# untitled.net
KiCad netlist of a schematic drawn in Altium Designer
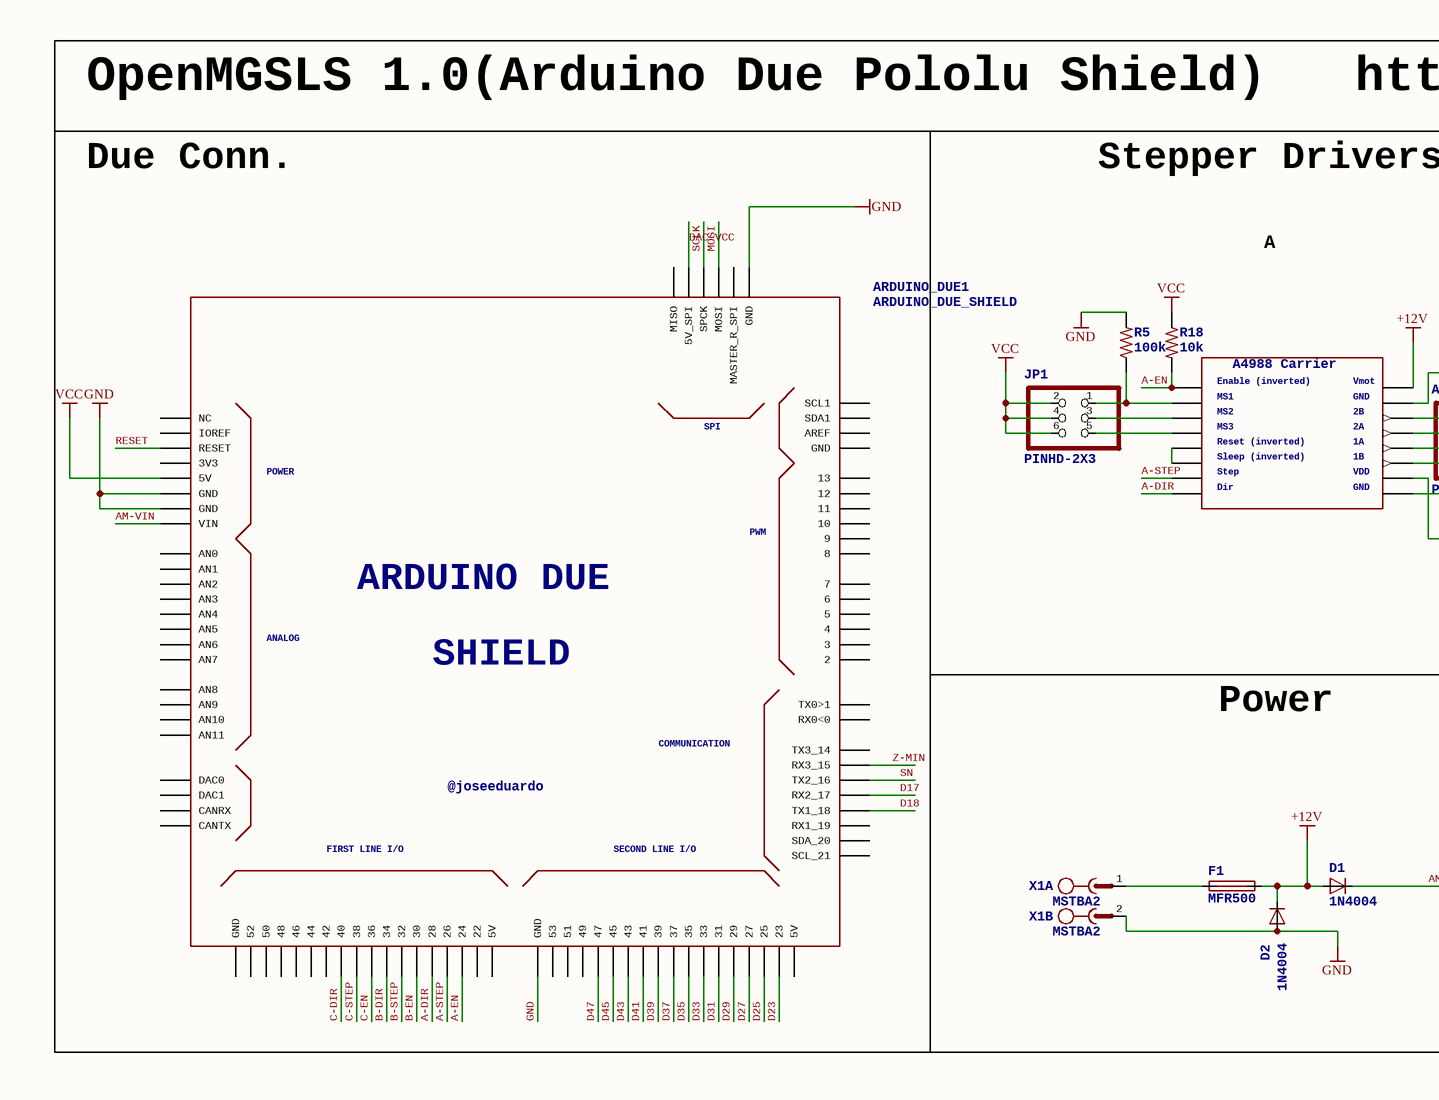
[diagram p0: untitled.SchDoc, left]
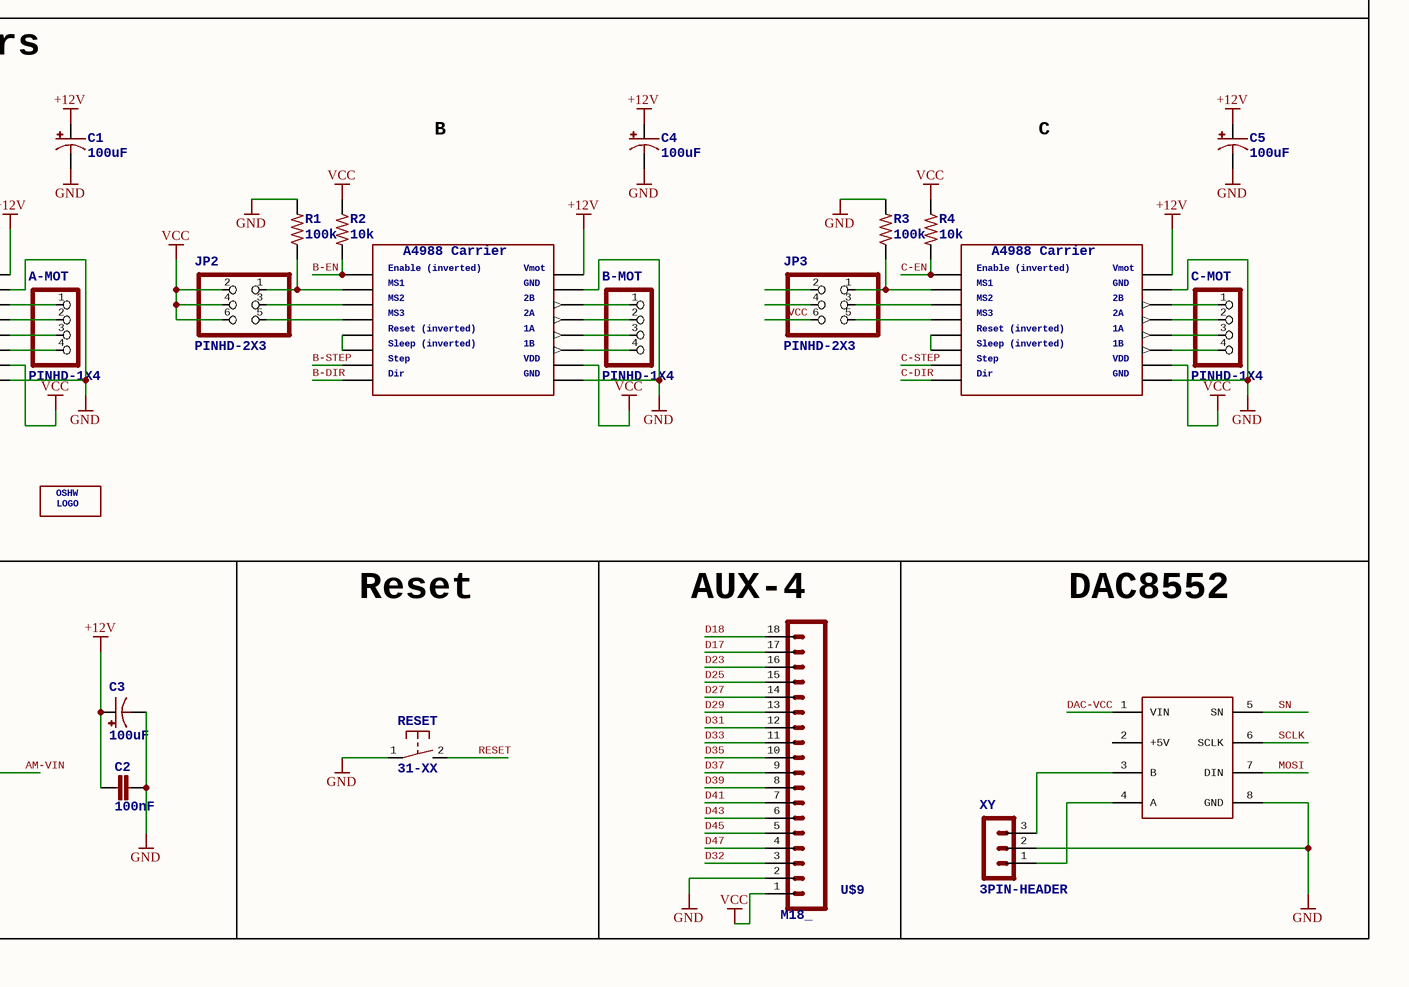
[diagram p1: untitled.SchDoc, right]

(export (version "E")
  (design (tool "Eeschema 10.0.6"))
  (components
    (comp (ref "A-MOT")
      (value "PINHD-1X4")
      (footprint "1X04")
      (description "PIN HEADER")
      (libsource (lib "RepRapjr") (part "PINHD-1X4"))
    )
    (comp (ref "ARDUINO_DUE1")
      (value "ARDUINO_DUE_SHIELD")
      (footprint "ARDUINO_DUE_SHIELD")
      (fields
        (field (name "ARDUINODUE") "ARDUINO DUE")
        (field (name "SHIELD") "SHIELD")
        (field (name "PWM") "PWM")
        (field (name "POWER") "POWER")
        (field (name "ANALOG") "ANALOG")
        (field (name "FIRSTLINEI/O") "FIRST LINE I/O")
        (field (name "SECONDLINEI/O") "SECOND LINE I/O")
        (field (name "COMMUNICATION") "COMMUNICATION")
        (field (name "SPI") "SPI")
        (field (name "@JOSEEDUARDO") "@joseeduardo")
      )
      (libsource (lib "RepRapjr") (part "ARDUINO_DUE_SHIELD"))
    )
    (comp (ref "B-MOT")
      (value "PINHD-1X4")
      (footprint "1X04")
      (description "PIN HEADER")
      (libsource (lib "RepRapjr") (part "PINHD-1X4"))
    )
    (comp (ref "C-MOT")
      (value "PINHD-1X4")
      (footprint "1X04")
      (description "PIN HEADER")
      (libsource (lib "RepRapjr") (part "PINHD-1X4"))
    )
    (comp (ref "C1")
      (value "100uF")
      (footprint "153CLV-0605")
      (description "POLARIZED CAPACITOR, American symbol")
      (libsource (lib "adafruit") (part "CPOL-US153CLV-0605"))
    )
    (comp (ref "C2")
      (value "100nF")
      (footprint "C0805")
      (description "CAPACITOR, European symbol")
      (libsource (lib "resistor") (part "C-EUC0805"))
    )
    (comp (ref "C3")
      (value "100uF")
      (footprint "153CLV-0605")
      (description "POLARIZED CAPACITOR, American symbol")
      (libsource (lib "") (part "CPOL-US153CLV-0605_1"))
    )
    (comp (ref "C4")
      (value "100uF")
      (footprint "153CLV-0605")
      (description "POLARIZED CAPACITOR, American symbol")
      (libsource (lib "adafruit") (part "CPOL-US153CLV-0605"))
    )
    (comp (ref "C5")
      (value "100uF")
      (footprint "153CLV-0605")
      (description "POLARIZED CAPACITOR, American symbol")
      (libsource (lib "adafruit") (part "CPOL-US153CLV-0605"))
    )
    (comp (ref "D1")
      (value "1N4004")
      (footprint "DO41-10")
      (description "DIODE   general purpose rectifier, 1 A")
      (libsource (lib "diode") (part "1N4004"))
    )
    (comp (ref "D2")
      (value "1N4004")
      (footprint "DO41-10")
      (description "DIODE   general purpose rectifier, 1 A")
      (libsource (lib "diode") (part "1N4004"))
    )
    (comp (ref "F1")
      (value "MFR500")
      (footprint "MFR500")
      (description "LITTLEFUSE   Picofuse/slow Littlefuse")
      (libsource (lib "RepRapjr") (part "PTCFUSE"))
    )
    (comp (ref "JP1")
      (value "PINHD-2X3")
      (footprint "2X03")
      (description "PIN HEADER")
      (libsource (lib "pinhead") (part "PINHD-2X3"))
    )
    (comp (ref "JP2")
      (value "PINHD-2X3")
      (footprint "2X03")
      (description "PIN HEADER")
      (libsource (lib "pinhead") (part "PINHD-2X3"))
    )
    (comp (ref "JP3")
      (value "PINHD-2X3")
      (footprint "2X03")
      (description "PIN HEADER")
      (libsource (lib "pinhead") (part "PINHD-2X3"))
    )
    (comp (ref "LOGO1")
      (value "OSHW_LOGO_6MILX0200-NT")
      (footprint "OSHW_6X200_NOTEXT")
      (fields (field (name "OSHW") "OSHW") (field (name "LOGO") "LOGO"))
      (libsource (lib "OSHW") (part "OSHW_LOGO_6MILX0200-NT"))
    )
    (comp (ref "R1")
      (value "100k")
      (footprint "R0805")
      (description "RESISTOR, American symbol")
      (libsource (lib "adafruit") (part "R-US_R0805"))
    )
    (comp (ref "R2")
      (value "10k")
      (footprint "R0805")
      (description "RESISTOR, American symbol")
      (libsource (lib "adafruit") (part "R-US_R0805"))
    )
    (comp (ref "R3")
      (value "100k")
      (footprint "R0805")
      (description "RESISTOR, American symbol")
      (libsource (lib "adafruit") (part "R-US_R0805"))
    )
    (comp (ref "R4")
      (value "10k")
      (footprint "R0805")
      (description "RESISTOR, American symbol")
      (libsource (lib "adafruit") (part "R-US_R0805"))
    )
    (comp (ref "R5")
      (value "100k")
      (footprint "R0805")
      (description "RESISTOR, American symbol")
      (libsource (lib "adafruit") (part "R-US_R0805"))
    )
    (comp (ref "R18")
      (value "10k")
      (footprint "R0805")
      (description "RESISTOR, American symbol")
      (libsource (lib "adafruit") (part "R-US_R0805"))
    )
    (comp (ref "RESET")
      (value "31-XX")
      (footprint "B3F-31XX")
      (description "OMRON SWITCH")
      (fields (field (name "MPN") "B3F-3100"))
      (libsource (lib "switch-omron") (part "31-XX"))
    )
    (comp (ref "U$1")
      (value "A4988BREAKOUT")
      (footprint "A4988BREAKOUT")
      (fields
        (field (name "GND") "GND")
        (field (name "ENABLE(INVERTED)") "Enable (inverted)")
        (field (name "MS1") "MS1")
        (field (name "MS2") "MS2")
        (field (name "MS3") "MS3")
        (field (name "RESET(INVERTED)") "Reset (inverted)")
        (field (name "SLEEP(INVERTED)") "Sleep (inverted)")
        (field (name "STEP") "Step")
        (field (name "DIR") "Dir")
        (field (name "VDD") "VDD")
        (field (name "VMOT") "Vmot")
        (field (name "GND_1") "GND")
        (field (name "2B") "2B")
        (field (name "2A") "2A")
        (field (name "1A") "1A")
        (field (name "1B") "1B")
        (field (name "A4988CARRIER") "A4988 Carrier")
      )
      (libsource (lib "RepRapjr") (part "A4988BREAKOUT"))
    )
    (comp (ref "U$2") (value "DAC8552") (footprint "DAC8552") (libsource (lib "RepRapjr") (part "DAC8552")))
    (comp (ref "U$3")
      (value "A4988BREAKOUT")
      (footprint "A4988BREAKOUT")
      (fields
        (field (name "GND") "GND")
        (field (name "ENABLE(INVERTED)") "Enable (inverted)")
        (field (name "MS1") "MS1")
        (field (name "MS2") "MS2")
        (field (name "MS3") "MS3")
        (field (name "RESET(INVERTED)") "Reset (inverted)")
        (field (name "SLEEP(INVERTED)") "Sleep (inverted)")
        (field (name "STEP") "Step")
        (field (name "DIR") "Dir")
        (field (name "VDD") "VDD")
        (field (name "VMOT") "Vmot")
        (field (name "GND_1") "GND")
        (field (name "2B") "2B")
        (field (name "2A") "2A")
        (field (name "1A") "1A")
        (field (name "1B") "1B")
        (field (name "A4988CARRIER") "A4988 Carrier")
      )
      (libsource (lib "RepRapjr") (part "A4988BREAKOUT"))
    )
    (comp (ref "U$6")
      (value "A4988BREAKOUT")
      (footprint "A4988BREAKOUT")
      (fields
        (field (name "GND") "GND")
        (field (name "ENABLE(INVERTED)") "Enable (inverted)")
        (field (name "MS1") "MS1")
        (field (name "MS2") "MS2")
        (field (name "MS3") "MS3")
        (field (name "RESET(INVERTED)") "Reset (inverted)")
        (field (name "SLEEP(INVERTED)") "Sleep (inverted)")
        (field (name "STEP") "Step")
        (field (name "DIR") "Dir")
        (field (name "VDD") "VDD")
        (field (name "VMOT") "Vmot")
        (field (name "GND_1") "GND")
        (field (name "2B") "2B")
        (field (name "2A") "2A")
        (field (name "1A") "1A")
        (field (name "1B") "1B")
        (field (name "A4988CARRIER") "A4988 Carrier")
      )
      (libsource (lib "RepRapjr") (part "A4988BREAKOUT"))
    )
    (comp (ref "U$9") (value "M18_") (footprint "1X18") (libsource (lib "SparkFun") (part "M18_")))
    (comp (ref "X1")
      (value "MSTBA2")
      (footprint "MSTBA2")
      (description "PHOENIX")
      (fields (field (name "MF") "FARNELL") (field (name "MPN") "1757242"))
      (libsource (lib "con-phoenix-508") (part "MSTBA2"))
    )
    (comp (ref "XY")
      (value "3PIN-HEADER")
      (footprint "3PIN-HEADER")
      (description "PIN HEADER")
      (libsource (lib "ultimachine") (part "3PIN-HEADER"))
    )
  )
  (nets
    (net (code "1") (name "+12V") (class "Default")
      (node (ref "C1") (pin "+") (pinfunction "+_+") (pintype "passive"))
      (node (ref "C2") (pin "1") (pinfunction "1_1") (pintype "passive"))
      (node (ref "C3") (pin "+") (pinfunction "+_+") (pintype "passive"))
      (node (ref "C4") (pin "+") (pinfunction "+_+") (pintype "passive"))
      (node (ref "C5") (pin "+") (pinfunction "+_+") (pintype "passive"))
      (node (ref "D1") (pin "A") (pinfunction "A_A") (pintype "passive"))
      (node (ref "D2") (pin "C") (pinfunction "C_C") (pintype "passive"))
      (node (ref "F1") (pin "1") (pinfunction "1_1") (pintype "passive"))
      (node (ref "U$1") (pin "VMOT") (pinfunction "VMOT_VMOT") (pintype "power_in"))
      (node (ref "U$3") (pin "VMOT") (pinfunction "VMOT_VMOT") (pintype "power_in"))
      (node (ref "U$6") (pin "VMOT") (pinfunction "VMOT_VMOT") (pintype "power_in"))
    )
    (net (code "2") (name "/A-DIR") (class "Default")
      (node (ref "ARDUINO_DUE1") (pin "28") (pinfunction "28_28") (pintype "passive"))
      (node (ref "U$6") (pin "DIR") (pinfunction "DIR_DIR") (pintype "passive"))
    )
    (net (code "3") (name "/A-EN") (class "Default")
      (node (ref "ARDUINO_DUE1") (pin "24") (pinfunction "24_24") (pintype "passive"))
      (node (ref "R18") (pin "2") (pinfunction "2_2") (pintype "passive"))
      (node (ref "U$6") (pin "EN") (pinfunction "EN_EN") (pintype "passive"))
    )
    (net (code "4") (name "/A-STEP") (class "Default")
      (node (ref "ARDUINO_DUE1") (pin "26") (pinfunction "26_26") (pintype "passive"))
      (node (ref "U$6") (pin "STEP") (pinfunction "STEP_STEP") (pintype "passive"))
    )
    (net (code "5") (name "/AM-VIN") (class "Default")
      (node (ref "ARDUINO_DUE1") (pin "VIN") (pinfunction "VIN_VIN") (pintype "passive"))
      (node (ref "D1") (pin "C") (pinfunction "C_C") (pintype "passive"))
    )
    (net (code "6") (name "/B-DIR") (class "Default")
      (node (ref "ARDUINO_DUE1") (pin "34") (pinfunction "34_34") (pintype "passive"))
      (node (ref "U$1") (pin "DIR") (pinfunction "DIR_DIR") (pintype "passive"))
    )
    (net (code "7") (name "/B-EN") (class "Default")
      (node (ref "ARDUINO_DUE1") (pin "30") (pinfunction "30_30") (pintype "passive"))
      (node (ref "R2") (pin "2") (pinfunction "2_2") (pintype "passive"))
      (node (ref "U$1") (pin "EN") (pinfunction "EN_EN") (pintype "passive"))
    )
    (net (code "8") (name "/B-STEP") (class "Default")
      (node (ref "ARDUINO_DUE1") (pin "32") (pinfunction "32_32") (pintype "passive"))
      (node (ref "U$1") (pin "STEP") (pinfunction "STEP_STEP") (pintype "passive"))
    )
    (net (code "9") (name "/C-DIR") (class "Default")
      (node (ref "ARDUINO_DUE1") (pin "40") (pinfunction "40_40") (pintype "passive"))
      (node (ref "U$3") (pin "DIR") (pinfunction "DIR_DIR") (pintype "passive"))
    )
    (net (code "10") (name "/C-EN") (class "Default")
      (node (ref "ARDUINO_DUE1") (pin "36") (pinfunction "36_36") (pintype "passive"))
      (node (ref "R4") (pin "2") (pinfunction "2_2") (pintype "passive"))
      (node (ref "U$3") (pin "EN") (pinfunction "EN_EN") (pintype "passive"))
    )
    (net (code "11") (name "/C-STEP") (class "Default")
      (node (ref "ARDUINO_DUE1") (pin "38") (pinfunction "38_38") (pintype "passive"))
      (node (ref "U$3") (pin "STEP") (pinfunction "STEP_STEP") (pintype "passive"))
    )
    (net (code "12") (name "/D17") (class "Default")
      (node (ref "ARDUINO_DUE1") (pin "17") (pinfunction "RX2_17_17") (pintype "passive"))
      (node (ref "U$9") (pin "17") (pinfunction "17_17") (pintype "passive"))
    )
    (net (code "13") (name "/D18") (class "Default")
      (node (ref "ARDUINO_DUE1") (pin "18") (pinfunction "TX1_18_18") (pintype "passive"))
      (node (ref "U$9") (pin "18") (pinfunction "18_18") (pintype "passive"))
    )
    (net (code "14") (name "/D23") (class "Default")
      (node (ref "ARDUINO_DUE1") (pin "23") (pinfunction "23_23") (pintype "passive"))
      (node (ref "U$9") (pin "16") (pinfunction "16_16") (pintype "passive"))
    )
    (net (code "15") (name "/D25") (class "Default")
      (node (ref "ARDUINO_DUE1") (pin "25") (pinfunction "25_25") (pintype "passive"))
      (node (ref "U$9") (pin "15") (pinfunction "15_15") (pintype "passive"))
    )
    (net (code "16") (name "/D27") (class "Default")
      (node (ref "ARDUINO_DUE1") (pin "27") (pinfunction "27_27") (pintype "passive"))
      (node (ref "U$9") (pin "14") (pinfunction "14_14") (pintype "passive"))
    )
    (net (code "17") (name "/D29") (class "Default")
      (node (ref "ARDUINO_DUE1") (pin "29") (pinfunction "29_29") (pintype "passive"))
      (node (ref "U$9") (pin "13") (pinfunction "13_13") (pintype "passive"))
    )
    (net (code "18") (name "/D31") (class "Default")
      (node (ref "ARDUINO_DUE1") (pin "31") (pinfunction "31_31") (pintype "passive"))
      (node (ref "U$9") (pin "12") (pinfunction "12_12") (pintype "passive"))
    )
    (net (code "19") (name "/D32") (class "Default")
      (node (ref "U$9") (pin "3") (pinfunction "3_3") (pintype "passive"))
    )
    (net (code "20") (name "/D33") (class "Default")
      (node (ref "ARDUINO_DUE1") (pin "33") (pinfunction "33_33") (pintype "passive"))
      (node (ref "U$9") (pin "11") (pinfunction "11_11") (pintype "passive"))
    )
    (net (code "21") (name "/D35") (class "Default")
      (node (ref "ARDUINO_DUE1") (pin "35") (pinfunction "35_35") (pintype "passive"))
      (node (ref "U$9") (pin "10") (pinfunction "10_10") (pintype "passive"))
    )
    (net (code "22") (name "/D37") (class "Default")
      (node (ref "ARDUINO_DUE1") (pin "37") (pinfunction "37_37") (pintype "passive"))
      (node (ref "U$9") (pin "9") (pinfunction "9_9") (pintype "passive"))
    )
    (net (code "23") (name "/D39") (class "Default")
      (node (ref "ARDUINO_DUE1") (pin "39") (pinfunction "39_39") (pintype "passive"))
      (node (ref "U$9") (pin "8") (pinfunction "8_8") (pintype "passive"))
    )
    (net (code "24") (name "/D41") (class "Default")
      (node (ref "ARDUINO_DUE1") (pin "41") (pinfunction "41_41") (pintype "passive"))
      (node (ref "U$9") (pin "7") (pinfunction "7_7") (pintype "passive"))
    )
    (net (code "25") (name "/D43") (class "Default")
      (node (ref "ARDUINO_DUE1") (pin "43") (pinfunction "43_43") (pintype "passive"))
      (node (ref "U$9") (pin "6") (pinfunction "6_6") (pintype "passive"))
    )
    (net (code "26") (name "/D45") (class "Default")
      (node (ref "ARDUINO_DUE1") (pin "45") (pinfunction "45_45") (pintype "passive"))
      (node (ref "U$9") (pin "5") (pinfunction "5_5") (pintype "passive"))
    )
    (net (code "27") (name "/D47") (class "Default")
      (node (ref "ARDUINO_DUE1") (pin "47") (pinfunction "47_47") (pintype "passive"))
      (node (ref "U$9") (pin "4") (pinfunction "4_4") (pintype "passive"))
    )
    (net (code "28") (name "/DAC-VCC") (class "Default")
      (node (ref "ARDUINO_DUE1") (pin "5V_2") (pinfunction "5V_SPI_5V_2") (pintype "passive"))
      (node (ref "U$2") (pin "1") (pinfunction "VIN_1") (pintype "passive"))
    )
    (net (code "29") (name "/MOSI") (class "Default")
      (node (ref "ARDUINO_DUE1") (pin "MOSI") (pinfunction "MOSI_MOSI") (pintype "passive"))
      (node (ref "U$2") (pin "7") (pinfunction "DIN_7") (pintype "passive"))
    )
    (net (code "30") (name "/RESET") (class "Default")
      (node (ref "ARDUINO_DUE1") (pin "RESET") (pinfunction "RESET_RESET") (pintype "passive"))
      (node (ref "RESET") (pin "2") (pinfunction "S_2") (pintype "passive"))
    )
    (net (code "31") (name "/SCLK") (class "Default")
      (node (ref "ARDUINO_DUE1") (pin "SPCK") (pinfunction "SPCK_SPCK") (pintype "passive"))
      (node (ref "U$2") (pin "6") (pinfunction "SCLK_6") (pintype "passive"))
    )
    (net (code "32") (name "/SN") (class "Default")
      (node (ref "ARDUINO_DUE1") (pin "16") (pinfunction "TX2_16_16") (pintype "passive"))
      (node (ref "U$2") (pin "5") (pinfunction "SN_5") (pintype "passive"))
    )
    (net (code "33") (name "/Z-MIN") (class "Default")
      (node (ref "ARDUINO_DUE1") (pin "15") (pinfunction "RX3_15_15") (pintype "passive"))
    )
    (net (code "34") (name "GND") (class "Default")
      (node (ref "ARDUINO_DUE1") (pin "GND") (pinfunction "GND_GND") (pintype "passive"))
      (node (ref "ARDUINO_DUE1") (pin "GND_1") (pinfunction "GND_GND_1") (pintype "passive"))
      (node (ref "ARDUINO_DUE1") (pin "GND_3") (pinfunction "GND_GND_3") (pintype "passive"))
      (node (ref "ARDUINO_DUE1") (pin "GND_5") (pinfunction "GND_GND_5") (pintype "passive"))
      (node (ref "C1") (pin "-") (pinfunction "-_-") (pintype "passive"))
      (node (ref "C2") (pin "2") (pinfunction "2_2") (pintype "passive"))
      (node (ref "C3") (pin "-") (pinfunction "-_-") (pintype "passive"))
      (node (ref "C4") (pin "-") (pinfunction "-_-") (pintype "passive"))
      (node (ref "C5") (pin "-") (pinfunction "-_-") (pintype "passive"))
      (node (ref "D2") (pin "A") (pinfunction "A_A") (pintype "passive"))
      (node (ref "R1") (pin "2") (pinfunction "2_2") (pintype "passive"))
      (node (ref "R3") (pin "2") (pinfunction "2_2") (pintype "passive"))
      (node (ref "R5") (pin "2") (pinfunction "2_2") (pintype "passive"))
      (node (ref "RESET") (pin "1") (pinfunction "P_1") (pintype "passive"))
      (node (ref "U$1") (pin "GND") (pinfunction "GND_GND") (pintype "power_in"))
      (node (ref "U$1") (pin "GND@0") (pinfunction "GND_GND@0") (pintype "power_in"))
      (node (ref "U$2") (pin "8") (pinfunction "GND_8") (pintype "passive"))
      (node (ref "U$3") (pin "GND") (pinfunction "GND_GND") (pintype "power_in"))
      (node (ref "U$3") (pin "GND@0") (pinfunction "GND_GND@0") (pintype "power_in"))
      (node (ref "U$6") (pin "GND") (pinfunction "GND_GND") (pintype "power_in"))
      (node (ref "U$6") (pin "GND@0") (pinfunction "GND_GND@0") (pintype "power_in"))
      (node (ref "U$9") (pin "2") (pinfunction "2_2") (pintype "passive"))
      (node (ref "X1") (pin "2") (pinfunction "1_2") (pintype "passive"))
      (node (ref "XY") (pin "2") (pinfunction "2_2") (pintype "passive"))
    )
    (net (code "35") (name "Net-(A-MOT-Pad1)") (class "Default")
      (node (ref "A-MOT") (pin "1") (pinfunction "1_1") (pintype "passive"))
      (node (ref "U$6") (pin "2B") (pinfunction "2B_2B") (pintype "output"))
    )
    (net (code "36") (name "Net-(A-MOT-Pad2)") (class "Default")
      (node (ref "A-MOT") (pin "2") (pinfunction "2_2") (pintype "passive"))
      (node (ref "U$6") (pin "2A") (pinfunction "2A_2A") (pintype "output"))
    )
    (net (code "37") (name "Net-(A-MOT-Pad3)") (class "Default")
      (node (ref "A-MOT") (pin "3") (pinfunction "3_3") (pintype "passive"))
      (node (ref "U$6") (pin "1A") (pinfunction "1A_1A") (pintype "output"))
    )
    (net (code "38") (name "Net-(A-MOT-Pad4)") (class "Default")
      (node (ref "A-MOT") (pin "4") (pinfunction "4_4") (pintype "passive"))
      (node (ref "U$6") (pin "1B") (pinfunction "1B_1B") (pintype "output"))
    )
    (net (code "39") (name "Net-(B-MOT-Pad1)") (class "Default")
      (node (ref "B-MOT") (pin "1") (pinfunction "1_1") (pintype "passive"))
      (node (ref "U$1") (pin "2B") (pinfunction "2B_2B") (pintype "output"))
    )
    (net (code "40") (name "Net-(B-MOT-Pad2)") (class "Default")
      (node (ref "B-MOT") (pin "2") (pinfunction "2_2") (pintype "passive"))
      (node (ref "U$1") (pin "2A") (pinfunction "2A_2A") (pintype "output"))
    )
    (net (code "41") (name "Net-(B-MOT-Pad3)") (class "Default")
      (node (ref "B-MOT") (pin "3") (pinfunction "3_3") (pintype "passive"))
      (node (ref "U$1") (pin "1A") (pinfunction "1A_1A") (pintype "output"))
    )
    (net (code "42") (name "Net-(B-MOT-Pad4)") (class "Default")
      (node (ref "B-MOT") (pin "4") (pinfunction "4_4") (pintype "passive"))
      (node (ref "U$1") (pin "1B") (pinfunction "1B_1B") (pintype "output"))
    )
    (net (code "43") (name "Net-(C-MOT-Pad1)") (class "Default")
      (node (ref "C-MOT") (pin "1") (pinfunction "1_1") (pintype "passive"))
      (node (ref "U$3") (pin "2B") (pinfunction "2B_2B") (pintype "output"))
    )
    (net (code "44") (name "Net-(C-MOT-Pad2)") (class "Default")
      (node (ref "C-MOT") (pin "2") (pinfunction "2_2") (pintype "passive"))
      (node (ref "U$3") (pin "2A") (pinfunction "2A_2A") (pintype "output"))
    )
    (net (code "45") (name "Net-(C-MOT-Pad3)") (class "Default")
      (node (ref "C-MOT") (pin "3") (pinfunction "3_3") (pintype "passive"))
      (node (ref "U$3") (pin "1A") (pinfunction "1A_1A") (pintype "output"))
    )
    (net (code "46") (name "Net-(C-MOT-Pad4)") (class "Default")
      (node (ref "C-MOT") (pin "4") (pinfunction "4_4") (pintype "passive"))
      (node (ref "U$3") (pin "1B") (pinfunction "1B_1B") (pintype "output"))
    )
    (net (code "47") (name "Net-(F1-Pad2)") (class "Default")
      (node (ref "F1") (pin "2") (pinfunction "2_2") (pintype "passive"))
      (node (ref "X1") (pin "1") (pinfunction "1_1") (pintype "passive"))
    )
    (net (code "48") (name "Net-(JP1-Pad1)") (class "Default")
      (node (ref "JP1") (pin "1") (pinfunction "1_1") (pintype "passive"))
      (node (ref "R5") (pin "1") (pinfunction "1_1") (pintype "passive"))
      (node (ref "U$6") (pin "MS1") (pinfunction "MS1_MS1") (pintype "passive"))
    )
    (net (code "49") (name "Net-(JP1-Pad3)") (class "Default")
      (node (ref "JP1") (pin "3") (pinfunction "3_3") (pintype "passive"))
      (node (ref "U$6") (pin "MS2") (pinfunction "MS2_MS2") (pintype "passive"))
    )
    (net (code "50") (name "Net-(JP1-Pad5)") (class "Default")
      (node (ref "JP1") (pin "5") (pinfunction "5_5") (pintype "passive"))
      (node (ref "U$6") (pin "MS3") (pinfunction "MS3_MS3") (pintype "passive"))
    )
    (net (code "51") (name "Net-(JP2-Pad1)") (class "Default")
      (node (ref "JP2") (pin "1") (pinfunction "1_1") (pintype "passive"))
      (node (ref "R1") (pin "1") (pinfunction "1_1") (pintype "passive"))
      (node (ref "U$1") (pin "MS1") (pinfunction "MS1_MS1") (pintype "passive"))
    )
    (net (code "52") (name "Net-(JP2-Pad3)") (class "Default")
      (node (ref "JP2") (pin "3") (pinfunction "3_3") (pintype "passive"))
      (node (ref "U$1") (pin "MS2") (pinfunction "MS2_MS2") (pintype "passive"))
    )
    (net (code "53") (name "Net-(JP2-Pad5)") (class "Default")
      (node (ref "JP2") (pin "5") (pinfunction "5_5") (pintype "passive"))
      (node (ref "U$1") (pin "MS3") (pinfunction "MS3_MS3") (pintype "passive"))
    )
    (net (code "54") (name "Net-(JP3-Pad1)") (class "Default")
      (node (ref "JP3") (pin "1") (pinfunction "1_1") (pintype "passive"))
      (node (ref "R3") (pin "1") (pinfunction "1_1") (pintype "passive"))
      (node (ref "U$3") (pin "MS1") (pinfunction "MS1_MS1") (pintype "passive"))
    )
    (net (code "55") (name "Net-(JP3-Pad3)") (class "Default")
      (node (ref "JP3") (pin "3") (pinfunction "3_3") (pintype "passive"))
      (node (ref "U$3") (pin "MS2") (pinfunction "MS2_MS2") (pintype "passive"))
    )
    (net (code "56") (name "Net-(JP3-Pad5)") (class "Default")
      (node (ref "JP3") (pin "5") (pinfunction "5_5") (pintype "passive"))
      (node (ref "U$3") (pin "MS3") (pinfunction "MS3_MS3") (pintype "passive"))
    )
    (net (code "57") (name "Net-(U$1-SLEEP)") (class "Default")
      (node (ref "U$1") (pin "RST") (pinfunction "RST_RST") (pintype "passive"))
      (node (ref "U$1") (pin "SLP") (pinfunction "SLEEP_SLP") (pintype "passive"))
    )
    (net (code "58") (name "Net-(U$2-A)") (class "Default")
      (node (ref "U$2") (pin "4") (pinfunction "A_4") (pintype "passive"))
      (node (ref "XY") (pin "1") (pinfunction "1_1") (pintype "passive"))
    )
    (net (code "59") (name "Net-(U$2-B)") (class "Default")
      (node (ref "U$2") (pin "3") (pinfunction "B_3") (pintype "passive"))
      (node (ref "XY") (pin "3") (pinfunction "3_3") (pintype "passive"))
    )
    (net (code "60") (name "Net-(U$3-SLEEP)") (class "Default")
      (node (ref "U$3") (pin "RST") (pinfunction "RST_RST") (pintype "passive"))
      (node (ref "U$3") (pin "SLP") (pinfunction "SLEEP_SLP") (pintype "passive"))
    )
    (net (code "61") (name "Net-(U$6-SLEEP)") (class "Default")
      (node (ref "U$6") (pin "RST") (pinfunction "RST_RST") (pintype "passive"))
      (node (ref "U$6") (pin "SLP") (pinfunction "SLEEP_SLP") (pintype "passive"))
    )
    (net (code "62") (name "VCC") (class "Default")
      (node (ref "ARDUINO_DUE1") (pin "5V0") (pinfunction "5V_5V0") (pintype "passive"))
      (node (ref "JP1") (pin "2") (pinfunction "2_2") (pintype "passive"))
      (node (ref "JP1") (pin "4") (pinfunction "4_4") (pintype "passive"))
      (node (ref "JP1") (pin "6") (pinfunction "6_6") (pintype "passive"))
      (node (ref "JP2") (pin "2") (pinfunction "2_2") (pintype "passive"))
      (node (ref "JP2") (pin "4") (pinfunction "4_4") (pintype "passive"))
      (node (ref "JP2") (pin "6") (pinfunction "6_6") (pintype "passive"))
      (node (ref "JP3") (pin "6") (pinfunction "6_6") (pintype "passive"))
      (node (ref "R18") (pin "1") (pinfunction "1_1") (pintype "passive"))
      (node (ref "R2") (pin "1") (pinfunction "1_1") (pintype "passive"))
      (node (ref "R4") (pin "1") (pinfunction "1_1") (pintype "passive"))
      (node (ref "U$1") (pin "VDD") (pinfunction "VDD_VDD") (pintype "power_in"))
      (node (ref "U$3") (pin "VDD") (pinfunction "VDD_VDD") (pintype "power_in"))
      (node (ref "U$6") (pin "VDD") (pinfunction "VDD_VDD") (pintype "power_in"))
      (node (ref "U$9") (pin "1") (pinfunction "1_1") (pintype "passive"))
    )
    (net (code "63") (name "unconnected-(ARDUINO_DUE1-5V-Pad5V0_1)") (class "Default")
      (node (ref "ARDUINO_DUE1") (pin "5V0_1") (pinfunction "5V_5V0_1") (pintype "passive"))
    )
    (net (code "64") (name "unconnected-(ARDUINO_DUE1-5V-Pad5V0_2)") (class "Default")
      (node (ref "ARDUINO_DUE1") (pin "5V0_2") (pinfunction "5V_5V0_2") (pintype "passive"))
    )
    (net (code "65") (name "unconnected-(ARDUINO_DUE1-AN0-PadA0)") (class "Default")
      (node (ref "ARDUINO_DUE1") (pin "A0") (pinfunction "AN0_A0") (pintype "passive"))
    )
    (net (code "66") (name "unconnected-(ARDUINO_DUE1-AN1-PadA1)") (class "Default")
      (node (ref "ARDUINO_DUE1") (pin "A1") (pinfunction "AN1_A1") (pintype "passive"))
    )
    (net (code "67") (name "unconnected-(ARDUINO_DUE1-AN2-PadA2)") (class "Default")
      (node (ref "ARDUINO_DUE1") (pin "A2") (pinfunction "AN2_A2") (pintype "passive"))
    )
    (net (code "68") (name "unconnected-(ARDUINO_DUE1-AN3-PadA3)") (class "Default")
      (node (ref "ARDUINO_DUE1") (pin "A3") (pinfunction "AN3_A3") (pintype "passive"))
    )
    (net (code "69") (name "unconnected-(ARDUINO_DUE1-AN4-PadA4)") (class "Default")
      (node (ref "ARDUINO_DUE1") (pin "A4") (pinfunction "AN4_A4") (pintype "passive"))
    )
    (net (code "70") (name "unconnected-(ARDUINO_DUE1-AN5-PadA5)") (class "Default")
      (node (ref "ARDUINO_DUE1") (pin "A5") (pinfunction "AN5_A5") (pintype "passive"))
    )
    (net (code "71") (name "unconnected-(ARDUINO_DUE1-AN6-PadA6)") (class "Default")
      (node (ref "ARDUINO_DUE1") (pin "A6") (pinfunction "AN6_A6") (pintype "passive"))
    )
    (net (code "72") (name "unconnected-(ARDUINO_DUE1-AN7-PadA7)") (class "Default")
      (node (ref "ARDUINO_DUE1") (pin "A7") (pinfunction "AN7_A7") (pintype "passive"))
    )
    (net (code "73") (name "unconnected-(ARDUINO_DUE1-AN8-PadA8)") (class "Default")
      (node (ref "ARDUINO_DUE1") (pin "A8") (pinfunction "AN8_A8") (pintype "passive"))
    )
    (net (code "74") (name "unconnected-(ARDUINO_DUE1-AN9-PadA9)") (class "Default")
      (node (ref "ARDUINO_DUE1") (pin "A9") (pinfunction "AN9_A9") (pintype "passive"))
    )
    (net (code "75") (name "unconnected-(ARDUINO_DUE1-AN10-PadA10)") (class "Default")
      (node (ref "ARDUINO_DUE1") (pin "A10") (pinfunction "AN10_A10") (pintype "passive"))
    )
    (net (code "76") (name "unconnected-(ARDUINO_DUE1-AN11-PadA11)") (class "Default")
      (node (ref "ARDUINO_DUE1") (pin "A11") (pinfunction "AN11_A11") (pintype "passive"))
    )
    (net (code "77") (name "unconnected-(ARDUINO_DUE1-GND-PadGND_2)") (class "Default")
      (node (ref "ARDUINO_DUE1") (pin "GND_2") (pinfunction "GND_GND_2") (pintype "passive"))
    )
    (net (code "78") (name "unconnected-(ARDUINO_DUE1-GND-PadGND_4)") (class "Default")
      (node (ref "ARDUINO_DUE1") (pin "GND_4") (pinfunction "GND_GND_4") (pintype "passive"))
    )
    (net (code "79") (name "unconnected-(ARDUINO_DUE1-MASTER_R_SPI-PadMASTER_RESET_SPI)") (class "Default")
      (node (ref "ARDUINO_DUE1") (pin "MASTER_RESET_SPI") (pinfunction "MASTER_R_SPI_MASTER_RESET_SPI") (pintype "passive"))
    )
    (net (code "80") (name "unconnected-(ARDUINO_DUE1-NC-PadNC_2)") (class "Default")
      (node (ref "ARDUINO_DUE1") (pin "NC_2") (pinfunction "NC_NC_2") (pintype "passive"))
    )
    (net (code "81") (name "unconnected-(ARDUINO_DUE1-Pad2)") (class "Default")
      (node (ref "ARDUINO_DUE1") (pin "2") (pinfunction "2_2") (pintype "passive"))
    )
    (net (code "82") (name "unconnected-(ARDUINO_DUE1-Pad3)") (class "Default")
      (node (ref "ARDUINO_DUE1") (pin "3") (pinfunction "3_3") (pintype "passive"))
    )
    (net (code "83") (name "unconnected-(ARDUINO_DUE1-Pad3V3)") (class "Default")
      (node (ref "ARDUINO_DUE1") (pin "3V3") (pinfunction "3V3_3V3") (pintype "passive"))
    )
    (net (code "84") (name "unconnected-(ARDUINO_DUE1-Pad4)") (class "Default")
      (node (ref "ARDUINO_DUE1") (pin "4") (pinfunction "4_4") (pintype "passive"))
    )
    (net (code "85") (name "unconnected-(ARDUINO_DUE1-Pad5)") (class "Default")
      (node (ref "ARDUINO_DUE1") (pin "5") (pinfunction "5_5") (pintype "passive"))
    )
    (net (code "86") (name "unconnected-(ARDUINO_DUE1-Pad6)") (class "Default")
      (node (ref "ARDUINO_DUE1") (pin "6") (pinfunction "6_6") (pintype "passive"))
    )
    (net (code "87") (name "unconnected-(ARDUINO_DUE1-Pad7)") (class "Default")
      (node (ref "ARDUINO_DUE1") (pin "7") (pinfunction "7_7") (pintype "passive"))
    )
    (net (code "88") (name "unconnected-(ARDUINO_DUE1-Pad8)") (class "Default")
      (node (ref "ARDUINO_DUE1") (pin "8") (pinfunction "8_8") (pintype "passive"))
    )
    (net (code "89") (name "unconnected-(ARDUINO_DUE1-Pad9)") (class "Default")
      (node (ref "ARDUINO_DUE1") (pin "9") (pinfunction "9_9") (pintype "passive"))
    )
    (net (code "90") (name "unconnected-(ARDUINO_DUE1-Pad10)") (class "Default")
      (node (ref "ARDUINO_DUE1") (pin "10") (pinfunction "10_10") (pintype "passive"))
    )
    (net (code "91") (name "unconnected-(ARDUINO_DUE1-Pad11)") (class "Default")
      (node (ref "ARDUINO_DUE1") (pin "11") (pinfunction "11_11") (pintype "passive"))
    )
    (net (code "92") (name "unconnected-(ARDUINO_DUE1-Pad12)") (class "Default")
      (node (ref "ARDUINO_DUE1") (pin "12") (pinfunction "12_12") (pintype "passive"))
    )
    (net (code "93") (name "unconnected-(ARDUINO_DUE1-Pad13)") (class "Default")
      (node (ref "ARDUINO_DUE1") (pin "13") (pinfunction "13_13") (pintype "passive"))
    )
    (net (code "94") (name "unconnected-(ARDUINO_DUE1-Pad22)") (class "Default")
      (node (ref "ARDUINO_DUE1") (pin "22") (pinfunction "22_22") (pintype "passive"))
    )
    (net (code "95") (name "unconnected-(ARDUINO_DUE1-Pad42)") (class "Default")
      (node (ref "ARDUINO_DUE1") (pin "42") (pinfunction "42_42") (pintype "passive"))
    )
    (net (code "96") (name "unconnected-(ARDUINO_DUE1-Pad44)") (class "Default")
      (node (ref "ARDUINO_DUE1") (pin "44") (pinfunction "44_44") (pintype "passive"))
    )
    (net (code "97") (name "unconnected-(ARDUINO_DUE1-Pad46)") (class "Default")
      (node (ref "ARDUINO_DUE1") (pin "46") (pinfunction "46_46") (pintype "passive"))
    )
    (net (code "98") (name "unconnected-(ARDUINO_DUE1-Pad48)") (class "Default")
      (node (ref "ARDUINO_DUE1") (pin "48") (pinfunction "48_48") (pintype "passive"))
    )
    (net (code "99") (name "unconnected-(ARDUINO_DUE1-Pad49)") (class "Default")
      (node (ref "ARDUINO_DUE1") (pin "49") (pinfunction "49_49") (pintype "passive"))
    )
    (net (code "100") (name "unconnected-(ARDUINO_DUE1-Pad50)") (class "Default")
      (node (ref "ARDUINO_DUE1") (pin "50") (pinfunction "50_50") (pintype "passive"))
    )
    (net (code "101") (name "unconnected-(ARDUINO_DUE1-Pad51)") (class "Default")
      (node (ref "ARDUINO_DUE1") (pin "51") (pinfunction "51_51") (pintype "passive"))
    )
    (net (code "102") (name "unconnected-(ARDUINO_DUE1-Pad52)") (class "Default")
      (node (ref "ARDUINO_DUE1") (pin "52") (pinfunction "52_52") (pintype "passive"))
    )
    (net (code "103") (name "unconnected-(ARDUINO_DUE1-Pad53)") (class "Default")
      (node (ref "ARDUINO_DUE1") (pin "53") (pinfunction "53_53") (pintype "passive"))
    )
    (net (code "104") (name "unconnected-(ARDUINO_DUE1-PadAREF)") (class "Default")
      (node (ref "ARDUINO_DUE1") (pin "AREF") (pinfunction "AREF_AREF") (pintype "passive"))
    )
    (net (code "105") (name "unconnected-(ARDUINO_DUE1-PadCANRX)") (class "Default")
      (node (ref "ARDUINO_DUE1") (pin "CANRX") (pinfunction "CANRX_CANRX") (pintype "passive"))
    )
    (net (code "106") (name "unconnected-(ARDUINO_DUE1-PadCANTX)") (class "Default")
      (node (ref "ARDUINO_DUE1") (pin "CANTX") (pinfunction "CANTX_CANTX") (pintype "passive"))
    )
    (net (code "107") (name "unconnected-(ARDUINO_DUE1-PadDAC0)") (class "Default")
      (node (ref "ARDUINO_DUE1") (pin "DAC0") (pinfunction "DAC0_DAC0") (pintype "passive"))
    )
    (net (code "108") (name "unconnected-(ARDUINO_DUE1-PadDAC1)") (class "Default")
      (node (ref "ARDUINO_DUE1") (pin "DAC1") (pinfunction "DAC1_DAC1") (pintype "passive"))
    )
    (net (code "109") (name "unconnected-(ARDUINO_DUE1-PadIOREF)") (class "Default")
      (node (ref "ARDUINO_DUE1") (pin "IOREF") (pinfunction "IOREF_IOREF") (pintype "passive"))
    )
    (net (code "110") (name "unconnected-(ARDUINO_DUE1-PadMISO)") (class "Default")
      (node (ref "ARDUINO_DUE1") (pin "MISO") (pinfunction "MISO_MISO") (pintype "passive"))
    )
    (net (code "111") (name "unconnected-(ARDUINO_DUE1-PadSCL1)") (class "Default")
      (node (ref "ARDUINO_DUE1") (pin "SCL1") (pinfunction "SCL1_SCL1") (pintype "passive"))
    )
    (net (code "112") (name "unconnected-(ARDUINO_DUE1-PadSDA1)") (class "Default")
      (node (ref "ARDUINO_DUE1") (pin "SDA1") (pinfunction "SDA1_SDA1") (pintype "passive"))
    )
    (net (code "113") (name "unconnected-(ARDUINO_DUE1-RX0<0-Pad0)") (class "Default")
      (node (ref "ARDUINO_DUE1") (pin "0") (pinfunction "RX0<0_0") (pintype "passive"))
    )
    (net (code "114") (name "unconnected-(ARDUINO_DUE1-RX1_19-Pad19)") (class "Default")
      (node (ref "ARDUINO_DUE1") (pin "19") (pinfunction "RX1_19_19") (pintype "passive"))
    )
    (net (code "115") (name "unconnected-(ARDUINO_DUE1-SCL_21-Pad21)") (class "Default")
      (node (ref "ARDUINO_DUE1") (pin "21") (pinfunction "SCL_21_21") (pintype "passive"))
    )
    (net (code "116") (name "unconnected-(ARDUINO_DUE1-SDA_20-Pad20)") (class "Default")
      (node (ref "ARDUINO_DUE1") (pin "20") (pinfunction "SDA_20_20") (pintype "passive"))
    )
    (net (code "117") (name "unconnected-(ARDUINO_DUE1-TX0>1-Pad1)") (class "Default")
      (node (ref "ARDUINO_DUE1") (pin "1") (pinfunction "TX0>1_1") (pintype "passive"))
    )
    (net (code "118") (name "unconnected-(ARDUINO_DUE1-TX3_14-Pad14)") (class "Default")
      (node (ref "ARDUINO_DUE1") (pin "14") (pinfunction "TX3_14_14") (pintype "passive"))
    )
    (net (code "119") (name "unconnected-(JP3-Pad2)") (class "Default")
      (node (ref "JP3") (pin "2") (pinfunction "2_2") (pintype "passive"))
    )
    (net (code "120") (name "unconnected-(JP3-Pad4)") (class "Default")
      (node (ref "JP3") (pin "4") (pinfunction "4_4") (pintype "passive"))
    )
    (net (code "121") (name "unconnected-(U$2-+5V-Pad2)") (class "Default")
      (node (ref "U$2") (pin "2") (pinfunction "+5V_2") (pintype "passive"))
    )
  )
)
